# T_Ringmod.net
KiCad netlist of a schematic drawn in EAGLE
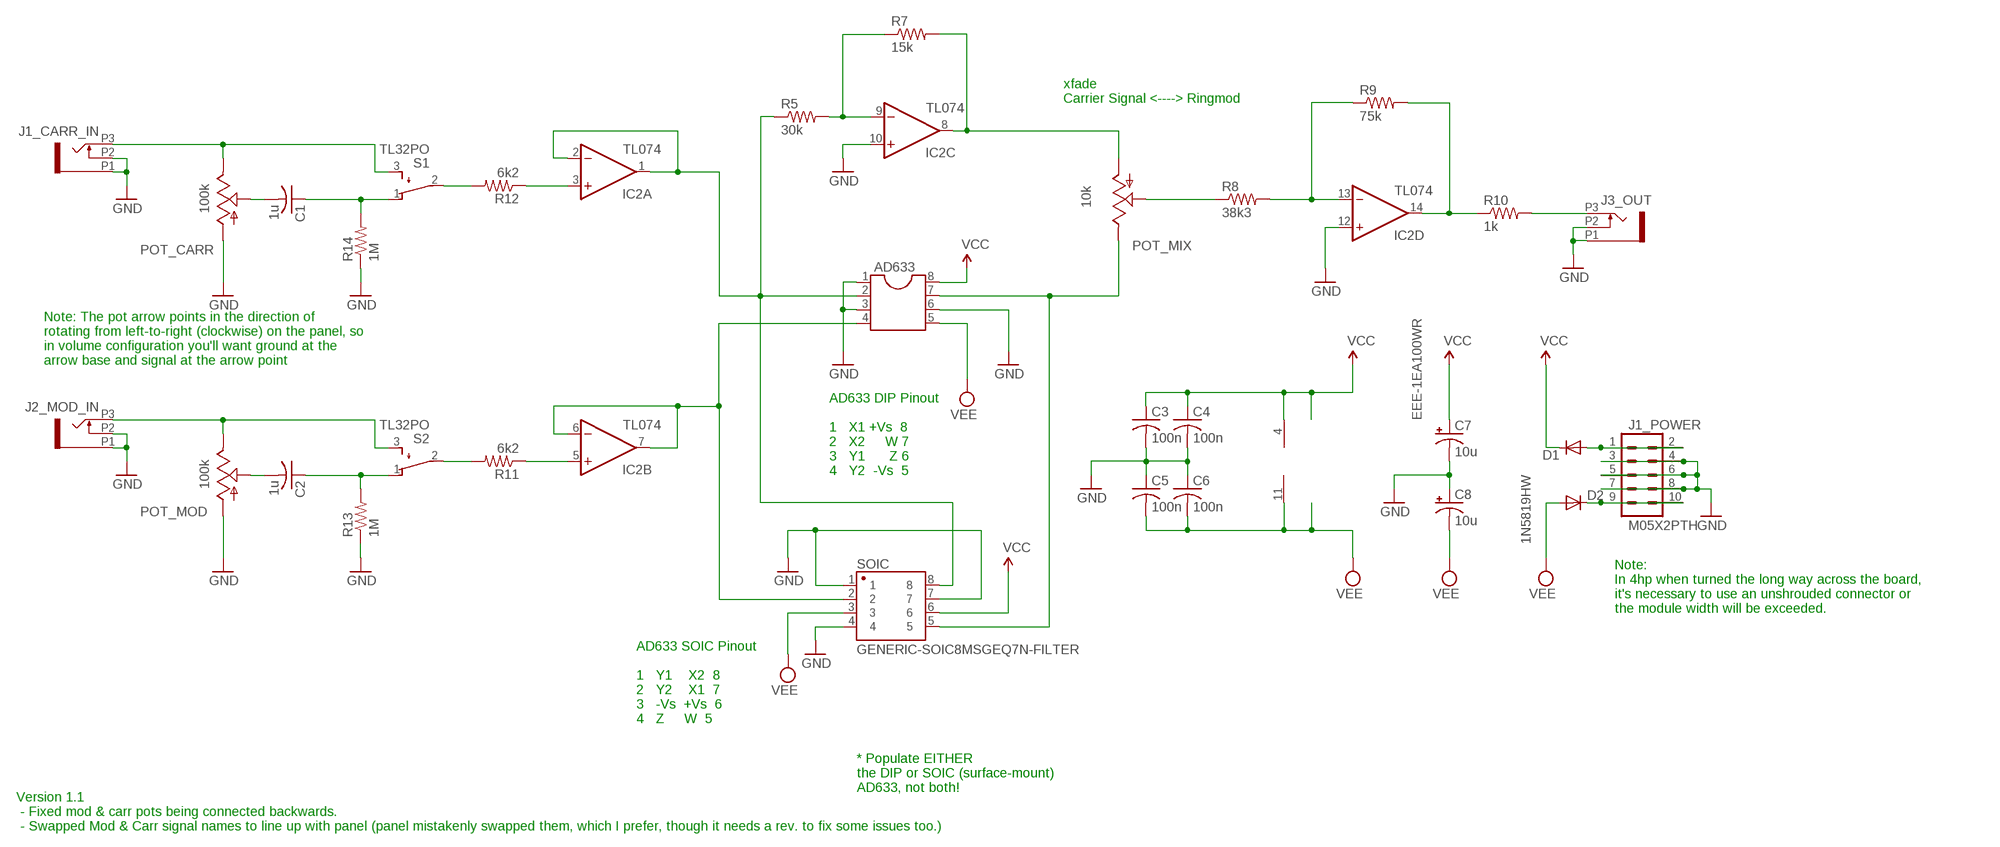
[diagram p0: schematic, sheet 1]

(export (version "E")
  (design (tool "Eeschema 10.0.6"))
  (components
    (comp (ref "AD633")
      (value "DIL8")
      (footprint "eagle-import:DIL08")
      (libsource (lib "eagle-import") (part "DIL8"))
    )
    (comp (ref "C1")
      (value "1u")
      (footprint "eagle-import:C0805")
      (libsource (lib "eagle-import") (part "C-USC0805"))
    )
    (comp (ref "C2")
      (value "1u")
      (footprint "eagle-import:C0805")
      (libsource (lib "eagle-import") (part "C-USC0805"))
    )
    (comp (ref "C3")
      (value "100n")
      (footprint "eagle-import:C0805")
      (libsource (lib "eagle-import") (part "C-USC0805"))
    )
    (comp (ref "C4")
      (value "100n")
      (footprint "eagle-import:C0805")
      (libsource (lib "eagle-import") (part "C-USC0805"))
    )
    (comp (ref "C5")
      (value "100n")
      (footprint "eagle-import:C0805")
      (libsource (lib "eagle-import") (part "C-USC0805"))
    )
    (comp (ref "C6")
      (value "100n")
      (footprint "eagle-import:C0805")
      (libsource (lib "eagle-import") (part "C-USC0805"))
    )
    (comp (ref "C7")
      (value "10u")
      (footprint "eagle-import:PANASONIC_A")
      (libsource (lib "eagle-import") (part "CPOL-USA"))
    )
    (comp (ref "C8")
      (value "10u")
      (footprint "eagle-import:PANASONIC_A")
      (libsource (lib "eagle-import") (part "CPOL-USA"))
    )
    (comp (ref "D1")
      (value "1N5819HW")
      (footprint "eagle-import:SOD123")
      (libsource (lib "eagle-import") (part "DIODE-SOD123"))
    )
    (comp (ref "D2")
      (value "1N5819HW")
      (footprint "eagle-import:SOD123")
      (libsource (lib "eagle-import") (part "DIODE-SOD123"))
    )
    (comp (ref "IC2")
      (value "TL074")
      (footprint "eagle-import:SO14")
      (libsource (lib "eagle-import") (part "TL074D"))
    )
    (comp (ref "J1_CARR_IN")
      (value "PJ301_THONKICONN6")
      (footprint "eagle-import:WQP_PJ_301M6")
      (libsource (lib "eagle-import") (part "PJ301_THONKICONN6"))
    )
    (comp (ref "J1_POWER")
      (value "M05X2PTH")
      (footprint "eagle-import:AVR_ICSP")
      (libsource (lib "eagle-import") (part "M05X2PTH"))
    )
    (comp (ref "J2_MOD_IN")
      (value "PJ301_THONKICONN6")
      (footprint "eagle-import:WQP_PJ_301M6")
      (libsource (lib "eagle-import") (part "PJ301_THONKICONN6"))
    )
    (comp (ref "J3_OUT")
      (value "PJ301_THONKICONN6")
      (footprint "eagle-import:WQP_PJ_301M6")
      (libsource (lib "eagle-import") (part "PJ301_THONKICONN6"))
    )
    (comp (ref "POT_CARR")
      (value "100k")
      (footprint "eagle-import:ALPS_POT_VERTICAL_PS")
      (libsource (lib "eagle-import") (part "POT_USVERTICAL_PS"))
    )
    (comp (ref "POT_MIX")
      (value "10k")
      (footprint "eagle-import:ALPS_POT_VERTICAL_PS")
      (libsource (lib "eagle-import") (part "POT_USVERTICAL_PS"))
    )
    (comp (ref "POT_MOD")
      (value "100k")
      (footprint "eagle-import:ALPS_POT_VERTICAL_PS")
      (libsource (lib "eagle-import") (part "POT_USVERTICAL_PS"))
    )
    (comp (ref "R5")
      (value "30k")
      (footprint "eagle-import:R0805")
      (libsource (lib "eagle-import") (part "R-US_R0805"))
    )
    (comp (ref "R7")
      (value "15k")
      (footprint "eagle-import:R0805")
      (libsource (lib "eagle-import") (part "R-US_R0805"))
    )
    (comp (ref "R8")
      (value "38k3")
      (footprint "eagle-import:R0805")
      (libsource (lib "eagle-import") (part "R-US_R0805"))
    )
    (comp (ref "R9")
      (value "75k")
      (footprint "eagle-import:R0805")
      (libsource (lib "eagle-import") (part "R-US_R0805"))
    )
    (comp (ref "R10")
      (value "1k")
      (footprint "eagle-import:R0805")
      (libsource (lib "eagle-import") (part "R-US_R0805"))
    )
    (comp (ref "R11")
      (value "6k2")
      (footprint "eagle-import:R0805")
      (libsource (lib "eagle-import") (part "R-US_R0805"))
    )
    (comp (ref "R12")
      (value "6k2")
      (footprint "eagle-import:R0805")
      (libsource (lib "eagle-import") (part "R-US_R0805"))
    )
    (comp (ref "R13")
      (value "1M")
      (footprint "eagle-import:R0805")
      (libsource (lib "eagle-import") (part "R-US_R0805"))
    )
    (comp (ref "R14")
      (value "1M")
      (footprint "eagle-import:R0805")
      (libsource (lib "eagle-import") (part "R-US_R0805"))
    )
    (comp (ref "S1")
      (value "TL32PO")
      (footprint "eagle-import:TL3XPO")
      (libsource (lib "eagle-import") (part "TL32PO"))
    )
    (comp (ref "S2")
      (value "TL32PO")
      (footprint "eagle-import:TL3XPO")
      (libsource (lib "eagle-import") (part "TL32PO"))
    )
    (comp (ref "SOIC")
      (value "GENERIC-SOIC8MSGEQ7N-FILTER")
      (footprint "eagle-import:SO08")
      (libsource (lib "eagle-import") (part "GENERIC-SOIC8MSGEQ7N-FILTER"))
    )
  )
  (nets
    (net (code "1") (name "GND") (class "Default")
      (node (ref "AD633") (pin "1") (pinfunction "1_1") (pintype "passive"))
      (node (ref "AD633") (pin "3") (pinfunction "3_3") (pintype "passive"))
      (node (ref "AD633") (pin "6") (pinfunction "6_6") (pintype "passive"))
      (node (ref "C3") (pin "2") (pinfunction "2_2") (pintype "passive"))
      (node (ref "C4") (pin "2") (pinfunction "2_2") (pintype "passive"))
      (node (ref "C5") (pin "1") (pinfunction "1_1") (pintype "passive"))
      (node (ref "C6") (pin "1") (pinfunction "1_1") (pintype "passive"))
      (node (ref "C7") (pin "-") (pinfunction "-_-") (pintype "passive"))
      (node (ref "C8") (pin "+") (pinfunction "+_+") (pintype "passive"))
      (node (ref "IC2") (pin "10") (pinfunction "+IN_10") (pintype "input"))
      (node (ref "IC2") (pin "12") (pinfunction "+IN_12") (pintype "input"))
      (node (ref "J1_CARR_IN") (pin "P1") (pinfunction "1_P1") (pintype "passive"))
      (node (ref "J1_CARR_IN") (pin "P2") (pinfunction "2_P2") (pintype "passive"))
      (node (ref "J1_POWER") (pin "3") (pinfunction "3_3") (pintype "passive"))
      (node (ref "J1_POWER") (pin "4") (pinfunction "4_4") (pintype "passive"))
      (node (ref "J1_POWER") (pin "5") (pinfunction "5_5") (pintype "passive"))
      (node (ref "J1_POWER") (pin "6") (pinfunction "6_6") (pintype "passive"))
      (node (ref "J1_POWER") (pin "7") (pinfunction "7_7") (pintype "passive"))
      (node (ref "J1_POWER") (pin "8") (pinfunction "8_8") (pintype "passive"))
      (node (ref "J2_MOD_IN") (pin "P1") (pinfunction "1_P1") (pintype "passive"))
      (node (ref "J2_MOD_IN") (pin "P2") (pinfunction "2_P2") (pintype "passive"))
      (node (ref "J3_OUT") (pin "P1") (pinfunction "1_P1") (pintype "passive"))
      (node (ref "J3_OUT") (pin "P2") (pinfunction "2_P2") (pintype "passive"))
      (node (ref "POT_CARR") (pin "P$3") (pinfunction "A_P$3") (pintype "passive"))
      (node (ref "POT_MOD") (pin "P$3") (pinfunction "A_P$3") (pintype "passive"))
      (node (ref "R13") (pin "1") (pinfunction "1_1") (pintype "passive"))
      (node (ref "R14") (pin "1") (pinfunction "1_1") (pintype "passive"))
      (node (ref "SOIC") (pin "1") (pinfunction "1_1") (pintype "bidirectional"))
      (node (ref "SOIC") (pin "4") (pinfunction "4_4") (pintype "bidirectional"))
      (node (ref "SOIC") (pin "7") (pinfunction "7_7") (pintype "bidirectional"))
    )
    (net (code "2") (name "Net-(D1-PadA)") (class "Default")
      (node (ref "D1") (pin "A") (pinfunction "A_A") (pintype "passive"))
      (node (ref "J1_POWER") (pin "1") (pinfunction "1_1") (pintype "passive"))
      (node (ref "J1_POWER") (pin "2") (pinfunction "2_2") (pintype "passive"))
    )
    (net (code "3") (name "Net-(D2-PadC)") (class "Default")
      (node (ref "D2") (pin "C") (pinfunction "C_C") (pintype "passive"))
      (node (ref "J1_POWER") (pin "10") (pinfunction "10_10") (pintype "passive"))
      (node (ref "J1_POWER") (pin "9") (pinfunction "9_9") (pintype "passive"))
    )
    (net (code "4") (name "Net-(IC2A-+IN)") (class "Default")
      (node (ref "IC2") (pin "3") (pinfunction "+IN_3") (pintype "input"))
      (node (ref "R12") (pin "1") (pinfunction "1_1") (pintype "passive"))
    )
    (net (code "5") (name "Net-(IC2A--IN)") (class "Default")
      (node (ref "AD633") (pin "2") (pinfunction "2_2") (pintype "passive"))
      (node (ref "IC2") (pin "1") (pinfunction "OUT_1") (pintype "output"))
      (node (ref "IC2") (pin "2") (pinfunction "-IN_2") (pintype "input"))
      (node (ref "R5") (pin "1") (pinfunction "1_1") (pintype "passive"))
      (node (ref "SOIC") (pin "8") (pinfunction "8_8") (pintype "bidirectional"))
    )
    (net (code "6") (name "Net-(IC2B-+IN)") (class "Default")
      (node (ref "IC2") (pin "5") (pinfunction "+IN_5") (pintype "input"))
      (node (ref "R11") (pin "1") (pinfunction "1_1") (pintype "passive"))
    )
    (net (code "7") (name "Net-(IC2B--IN)") (class "Default")
      (node (ref "AD633") (pin "4") (pinfunction "4_4") (pintype "passive"))
      (node (ref "IC2") (pin "6") (pinfunction "-IN_6") (pintype "input"))
      (node (ref "IC2") (pin "7") (pinfunction "OUT_7") (pintype "output"))
      (node (ref "SOIC") (pin "2") (pinfunction "2_2") (pintype "bidirectional"))
    )
    (net (code "8") (name "Net-(IC2C--IN)") (class "Default")
      (node (ref "IC2") (pin "9") (pinfunction "-IN_9") (pintype "input"))
      (node (ref "R5") (pin "2") (pinfunction "2_2") (pintype "passive"))
      (node (ref "R7") (pin "1") (pinfunction "1_1") (pintype "passive"))
    )
    (net (code "9") (name "Net-(IC2C-OUT)") (class "Default")
      (node (ref "IC2") (pin "8") (pinfunction "OUT_8") (pintype "output"))
      (node (ref "POT_MIX") (pin "P$3") (pinfunction "A_P$3") (pintype "passive"))
      (node (ref "R7") (pin "2") (pinfunction "2_2") (pintype "passive"))
    )
    (net (code "10") (name "Net-(IC2D--IN)") (class "Default")
      (node (ref "IC2") (pin "13") (pinfunction "-IN_13") (pintype "input"))
      (node (ref "R8") (pin "2") (pinfunction "2_2") (pintype "passive"))
      (node (ref "R9") (pin "1") (pinfunction "1_1") (pintype "passive"))
    )
    (net (code "11") (name "Net-(IC2D-OUT)") (class "Default")
      (node (ref "IC2") (pin "14") (pinfunction "OUT_14") (pintype "output"))
      (node (ref "R10") (pin "1") (pinfunction "1_1") (pintype "passive"))
      (node (ref "R9") (pin "2") (pinfunction "2_2") (pintype "passive"))
    )
    (net (code "12") (name "Net-(J1_CARR_IN-3)") (class "Default")
      (node (ref "J1_CARR_IN") (pin "P3") (pinfunction "3_P3") (pintype "passive"))
      (node (ref "POT_CARR") (pin "P$1") (pinfunction "E_P$1") (pintype "passive"))
      (node (ref "S1") (pin "3") (pinfunction "S_3") (pintype "passive"))
    )
    (net (code "13") (name "Net-(J2_MOD_IN-3)") (class "Default")
      (node (ref "J2_MOD_IN") (pin "P3") (pinfunction "3_P3") (pintype "passive"))
      (node (ref "POT_MOD") (pin "P$1") (pinfunction "E_P$1") (pintype "passive"))
      (node (ref "S2") (pin "3") (pinfunction "S_3") (pintype "passive"))
    )
    (net (code "14") (name "Net-(J3_OUT-3)") (class "Default")
      (node (ref "J3_OUT") (pin "P3") (pinfunction "3_P3") (pintype "passive"))
      (node (ref "R10") (pin "2") (pinfunction "2_2") (pintype "passive"))
    )
    (net (code "15") (name "Net-(POT_CARR-S)") (class "Default")
      (node (ref "C1") (pin "2") (pinfunction "2_2") (pintype "passive"))
      (node (ref "POT_CARR") (pin "P$2") (pinfunction "S_P$2") (pintype "passive"))
    )
    (net (code "16") (name "Net-(POT_MIX-E)") (class "Default")
      (node (ref "AD633") (pin "7") (pinfunction "7_7") (pintype "passive"))
      (node (ref "POT_MIX") (pin "P$1") (pinfunction "E_P$1") (pintype "passive"))
      (node (ref "SOIC") (pin "5") (pinfunction "5_5") (pintype "bidirectional"))
    )
    (net (code "17") (name "Net-(POT_MIX-S)") (class "Default")
      (node (ref "POT_MIX") (pin "P$2") (pinfunction "S_P$2") (pintype "passive"))
      (node (ref "R8") (pin "1") (pinfunction "1_1") (pintype "passive"))
    )
    (net (code "18") (name "Net-(POT_MOD-S)") (class "Default")
      (node (ref "C2") (pin "2") (pinfunction "2_2") (pintype "passive"))
      (node (ref "POT_MOD") (pin "P$2") (pinfunction "S_P$2") (pintype "passive"))
    )
    (net (code "19") (name "Net-(S1-O)") (class "Default")
      (node (ref "C1") (pin "1") (pinfunction "1_1") (pintype "passive"))
      (node (ref "R14") (pin "2") (pinfunction "2_2") (pintype "passive"))
      (node (ref "S1") (pin "1") (pinfunction "O_1") (pintype "passive"))
    )
    (net (code "20") (name "Net-(S1-P)") (class "Default")
      (node (ref "R12") (pin "2") (pinfunction "2_2") (pintype "passive"))
      (node (ref "S1") (pin "2") (pinfunction "P_2") (pintype "passive"))
    )
    (net (code "21") (name "Net-(S2-O)") (class "Default")
      (node (ref "C2") (pin "1") (pinfunction "1_1") (pintype "passive"))
      (node (ref "R13") (pin "2") (pinfunction "2_2") (pintype "passive"))
      (node (ref "S2") (pin "1") (pinfunction "O_1") (pintype "passive"))
    )
    (net (code "22") (name "Net-(S2-P)") (class "Default")
      (node (ref "R11") (pin "2") (pinfunction "2_2") (pintype "passive"))
      (node (ref "S2") (pin "2") (pinfunction "P_2") (pintype "passive"))
    )
    (net (code "23") (name "VCC") (class "Default")
      (node (ref "AD633") (pin "8") (pinfunction "8_8") (pintype "passive"))
      (node (ref "C3") (pin "1") (pinfunction "1_1") (pintype "passive"))
      (node (ref "C4") (pin "1") (pinfunction "1_1") (pintype "passive"))
      (node (ref "C7") (pin "+") (pinfunction "+_+") (pintype "passive"))
      (node (ref "D1") (pin "C") (pinfunction "C_C") (pintype "passive"))
      (node (ref "IC2") (pin "4") (pinfunction "V+_4") (pintype "power_in"))
      (node (ref "SOIC") (pin "6") (pinfunction "6_6") (pintype "bidirectional"))
    )
    (net (code "24") (name "VEE") (class "Default")
      (node (ref "AD633") (pin "5") (pinfunction "5_5") (pintype "passive"))
      (node (ref "C5") (pin "2") (pinfunction "2_2") (pintype "passive"))
      (node (ref "C6") (pin "2") (pinfunction "2_2") (pintype "passive"))
      (node (ref "C8") (pin "-") (pinfunction "-_-") (pintype "passive"))
      (node (ref "D2") (pin "A") (pinfunction "A_A") (pintype "passive"))
      (node (ref "IC2") (pin "11") (pinfunction "V-_11") (pintype "power_in"))
      (node (ref "SOIC") (pin "3") (pinfunction "3_3") (pintype "bidirectional"))
    )
  )
)
